# GPS_radiologger_v5_b.net
KiCad netlist of a schematic drawn in EAGLE
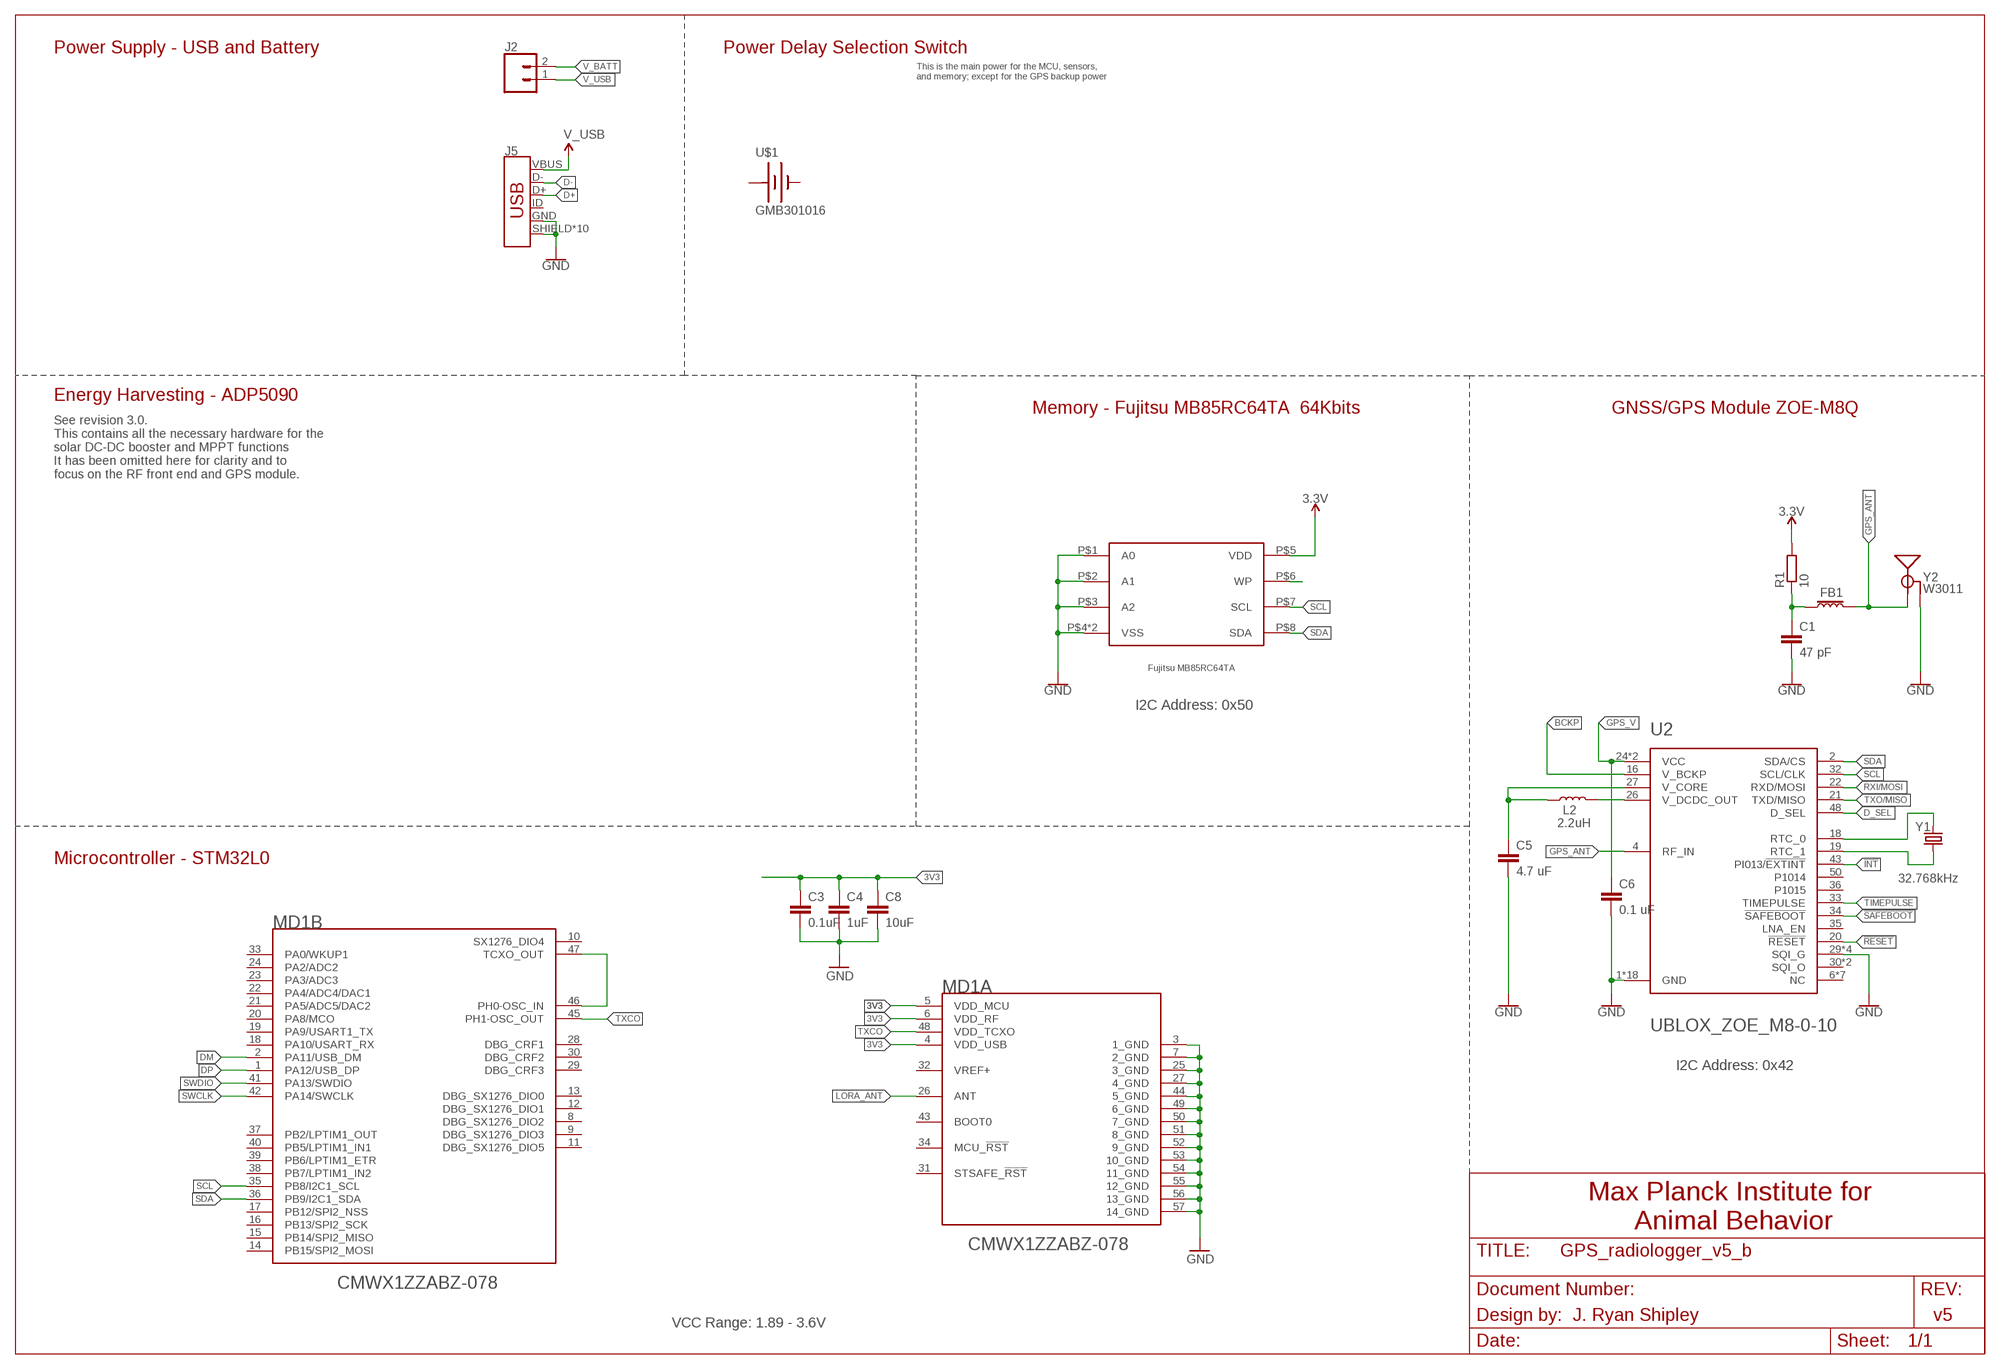
[diagram p0: schematic, sheet 1]

(export (version "E")
  (design (tool "Eeschema 10.0.6"))
  (components
    (comp (ref "C1")
      (value "47 pF")
      (footprint "eagle-import:C0201")
      (libsource (lib "eagle-import") (part "C-EUC0201"))
    )
    (comp (ref "C3")
      (value "0.1uF")
      (footprint "eagle-import:C0201")
      (libsource (lib "eagle-import") (part "C-EUC0201"))
    )
    (comp (ref "C4")
      (value "1uF")
      (footprint "eagle-import:C0201")
      (libsource (lib "eagle-import") (part "C-EUC0201"))
    )
    (comp (ref "C5")
      (value "4.7 uF")
      (footprint "eagle-import:C0201")
      (libsource (lib "eagle-import") (part "C-EUC0201"))
    )
    (comp (ref "C6")
      (value "0.1 uF")
      (footprint "eagle-import:C0201")
      (libsource (lib "eagle-import") (part "C-EUC0201"))
    )
    (comp (ref "C8")
      (value "10uF")
      (footprint "eagle-import:C0201")
      (libsource (lib "eagle-import") (part "C-EUC0201"))
    )
    (comp (ref "FB1")
      (value "FERRITE_BEAD-120_OHM-0402")
      (footprint "eagle-import:0402")
      (fields (field (name "MFG_PART") "BLM15HB121SN1D"))
      (libsource (lib "eagle-import") (part "FERRITE_BEAD-120_OHM-0402"))
    )
    (comp (ref "J2")
      (value "CONN_02")
      (footprint "eagle-import:1X02")
      (libsource (lib "eagle-import") (part "CONN_02"))
    )
    (comp (ref "J5")
      (value "USB_MICRO-B_HALF_PTH_MILL")
      (footprint "eagle-import:USB-MICROB-PTH-MILL")
      (libsource (lib "eagle-import") (part "USB_MICRO-B_HALF_PTH_MILL"))
    )
    (comp (ref "L2")
      (value "2.2uH")
      (footprint "eagle-import:0806")
      (libsource (lib "eagle-import") (part "2.2μH_SHIELDED_INDUCTOR"))
    )
    (comp (ref "MD1")
      (value "MURATA_CMWX1ZZABZ-078MURATA_CMWX1ZZABZ-078_0_0")
      (footprint "eagle-import:MURATA_CMWX1ZZABZ-078_0")
      (fields
        (field (name "DIGIKEY_PART_NUMBER") "490-16143-1-ND")
        (field (name "MF") "Murata")
        (field (name "MOUSER_PART_NUMBER") "81-CMWX1ZZABZ-078")
      )
      (libsource (lib "eagle-import") (part "MURATA_CMWX1ZZABZ-078MURATA_CMWX1ZZABZ-078_0_0"))
    )
    (comp (ref "R1")
      (value "10")
      (footprint "eagle-import:R0201")
      (libsource (lib "eagle-import") (part "R-EU_R0201"))
    )
    (comp (ref "U$1")
      (value "GMB301016")
      (footprint "eagle-import:GMB301016")
      (libsource (lib "eagle-import") (part "GMB301016"))
    )
    (comp (ref "U$2")
      (value "MB85RC64TA")
      (footprint "eagle-import:8-SON_2X3")
      (libsource (lib "eagle-import") (part "MB85RC64TA"))
    )
    (comp (ref "U2")
      (value "UBLOX_ZOE_M8-0-10")
      (footprint "eagle-import:UBLOX_ZOE_M8-0-10")
      (libsource (lib "eagle-import") (part "UBLOX_ZOE_M8-0-10"))
    )
    (comp (ref "Y1")
      (value "32.768kHz")
      (footprint "eagle-import:CRYSTAL-SMD-3.2X1.5MM")
      (libsource (lib "eagle-import") (part "CRYSTAL-32.768KHZSMD-3.2X1.5"))
    )
    (comp (ref "Y2")
      (value "W3011")
      (footprint "eagle-import:W3011")
      (libsource (lib "eagle-import") (part "GPS_CHIP_ANTENNAW3011"))
    )
  )
  (nets
    (net (code "1") (name "/+") (class "Default")
      (node (ref "U$1") (pin "+") (pinfunction "+_+") (pintype "power_in"))
    )
    (net (code "2") (name "/-") (class "Default")
      (node (ref "U$1") (pin "-") (pinfunction "-_-") (pintype "power_in"))
    )
    (net (code "3") (name "/VREF+") (class "Default")
      (node (ref "MD1") (pin "32") (pinfunction "VREF+_32") (pintype "power_in"))
    )
    (net (code "4") (name "/~{INT}") (class "Default")
      (node (ref "U2") (pin "43") (pinfunction "PI013/~{EXTINT}_43") (pintype "bidirectional"))
    )
    (net (code "5") (name "/~{RESET}") (class "Default")
      (node (ref "U2") (pin "20") (pinfunction "~{RESET}_20") (pintype "bidirectional"))
    )
    (net (code "6") (name "/~{SAFEBOOT}") (class "Default")
      (node (ref "U2") (pin "34") (pinfunction "~{SAFEBOOT}_34") (pintype "bidirectional"))
    )
    (net (code "7") (name "3.3V") (class "Default")
      (node (ref "R1") (pin "2") (pinfunction "2_2") (pintype "passive"))
      (node (ref "U$2") (pin "P$5") (pinfunction "VDD_P$5") (pintype "bidirectional"))
    )
    (net (code "8") (name "3V3") (class "Default")
      (node (ref "C3") (pin "1") (pinfunction "1_1") (pintype "passive"))
      (node (ref "C4") (pin "1") (pinfunction "1_1") (pintype "passive"))
      (node (ref "C8") (pin "1") (pinfunction "1_1") (pintype "passive"))
      (node (ref "MD1") (pin "4") (pinfunction "VDD_USB_4") (pintype "power_in"))
      (node (ref "MD1") (pin "5") (pinfunction "VDD_MCU_5") (pintype "power_in"))
      (node (ref "MD1") (pin "6") (pinfunction "VDD_RF_6") (pintype "power_in"))
    )
    (net (code "9") (name "BCKP") (class "Default")
      (node (ref "U2") (pin "16") (pinfunction "V_BCKP_16") (pintype "power_in"))
    )
    (net (code "10") (name "D+") (class "Default")
      (node (ref "J5") (pin "D+") (pinfunction "D+_D+") (pintype "bidirectional"))
    )
    (net (code "11") (name "D-") (class "Default")
      (node (ref "J5") (pin "D-") (pinfunction "D-_D-") (pintype "bidirectional"))
    )
    (net (code "12") (name "DM") (class "Default")
      (node (ref "MD1") (pin "2") (pinfunction "PA11/USB_DM_2") (pintype "bidirectional"))
    )
    (net (code "13") (name "DP") (class "Default")
      (node (ref "MD1") (pin "1") (pinfunction "PA12/USB_DP_1") (pintype "bidirectional"))
    )
    (net (code "14") (name "D_SEL") (class "Default")
      (node (ref "U2") (pin "48") (pinfunction "D_SEL_48") (pintype "bidirectional"))
    )
    (net (code "15") (name "GND") (class "Default")
      (node (ref "C1") (pin "2") (pinfunction "2_2") (pintype "passive"))
      (node (ref "C3") (pin "2") (pinfunction "2_2") (pintype "passive"))
      (node (ref "C4") (pin "2") (pinfunction "2_2") (pintype "passive"))
      (node (ref "C5") (pin "2") (pinfunction "2_2") (pintype "passive"))
      (node (ref "C6") (pin "2") (pinfunction "2_2") (pintype "passive"))
      (node (ref "C8") (pin "2") (pinfunction "2_2") (pintype "passive"))
      (node (ref "J5") (pin "GND") (pinfunction "GND_GND") (pintype "power_in"))
      (node (ref "J5") (pin "SHIELD") (pinfunction "SHIELD_SHIELD") (pintype "bidirectional"))
      (node (ref "J5") (pin "SHIELD10") (pinfunction "SHIELD_SHIELD10") (pintype "bidirectional"))
      (node (ref "J5") (pin "SHIELD2") (pinfunction "SHIELD_SHIELD2") (pintype "bidirectional"))
      (node (ref "J5") (pin "SHIELD3") (pinfunction "SHIELD_SHIELD3") (pintype "bidirectional"))
      (node (ref "J5") (pin "SHIELD4") (pinfunction "SHIELD_SHIELD4") (pintype "bidirectional"))
      (node (ref "J5") (pin "SHIELD5") (pinfunction "SHIELD_SHIELD5") (pintype "bidirectional"))
      (node (ref "J5") (pin "SHIELD6") (pinfunction "SHIELD_SHIELD6") (pintype "bidirectional"))
      (node (ref "J5") (pin "SHIELD7") (pinfunction "SHIELD_SHIELD7") (pintype "bidirectional"))
      (node (ref "J5") (pin "SHIELD8") (pinfunction "SHIELD_SHIELD8") (pintype "bidirectional"))
      (node (ref "J5") (pin "SHIELD9") (pinfunction "SHIELD_SHIELD9") (pintype "bidirectional"))
      (node (ref "MD1") (pin "25") (pinfunction "3_GND_25") (pintype "power_in"))
      (node (ref "MD1") (pin "27") (pinfunction "4_GND_27") (pintype "power_in"))
      (node (ref "MD1") (pin "3") (pinfunction "1_GND_3") (pintype "power_in"))
      (node (ref "MD1") (pin "44") (pinfunction "5_GND_44") (pintype "power_in"))
      (node (ref "MD1") (pin "49") (pinfunction "6_GND_49") (pintype "power_in"))
      (node (ref "MD1") (pin "50") (pinfunction "7_GND_50") (pintype "power_in"))
      (node (ref "MD1") (pin "51") (pinfunction "8_GND_51") (pintype "power_in"))
      (node (ref "MD1") (pin "52") (pinfunction "9_GND_52") (pintype "power_in"))
      (node (ref "MD1") (pin "53") (pinfunction "10_GND_53") (pintype "power_in"))
      (node (ref "MD1") (pin "54") (pinfunction "11_GND_54") (pintype "power_in"))
      (node (ref "MD1") (pin "55") (pinfunction "12_GND_55") (pintype "power_in"))
      (node (ref "MD1") (pin "56") (pinfunction "13_GND_56") (pintype "power_in"))
      (node (ref "MD1") (pin "57") (pinfunction "14_GND_57") (pintype "power_in"))
      (node (ref "MD1") (pin "7") (pinfunction "2_GND_7") (pintype "power_in"))
      (node (ref "U$2") (pin "P$1") (pinfunction "A0_P$1") (pintype "bidirectional"))
      (node (ref "U$2") (pin "P$2") (pinfunction "A1_P$2") (pintype "bidirectional"))
      (node (ref "U$2") (pin "P$3") (pinfunction "A2_P$3") (pintype "bidirectional"))
      (node (ref "U$2") (pin "P$4") (pinfunction "VSS_P$4") (pintype "bidirectional"))
      (node (ref "U$2") (pin "P$9") (pinfunction "VSS_P$9") (pintype "bidirectional"))
      (node (ref "U2") (pin "1") (pinfunction "GND_1") (pintype "power_in"))
      (node (ref "U2") (pin "10") (pinfunction "GND_10") (pintype "power_in"))
      (node (ref "U2") (pin "11") (pinfunction "GND_11") (pintype "power_in"))
      (node (ref "U2") (pin "12") (pinfunction "GND_12") (pintype "power_in"))
      (node (ref "U2") (pin "17") (pinfunction "GND_17") (pintype "power_in"))
      (node (ref "U2") (pin "23") (pinfunction "GND_23") (pintype "power_in"))
      (node (ref "U2") (pin "29") (pinfunction "SQI_G_29") (pintype "bidirectional"))
      (node (ref "U2") (pin "3") (pinfunction "GND_3") (pintype "power_in"))
      (node (ref "U2") (pin "31") (pinfunction "SQI_G_31") (pintype "bidirectional"))
      (node (ref "U2") (pin "37") (pinfunction "GND_37") (pintype "power_in"))
      (node (ref "U2") (pin "38") (pinfunction "GND_38") (pintype "power_in"))
      (node (ref "U2") (pin "39") (pinfunction "GND_39") (pintype "power_in"))
      (node (ref "U2") (pin "40") (pinfunction "GND_40") (pintype "power_in"))
      (node (ref "U2") (pin "41") (pinfunction "GND_41") (pintype "power_in"))
      (node (ref "U2") (pin "44") (pinfunction "GND_44") (pintype "power_in"))
      (node (ref "U2") (pin "46") (pinfunction "SQI_G_46") (pintype "bidirectional"))
      (node (ref "U2") (pin "47") (pinfunction "SQI_G_47") (pintype "bidirectional"))
      (node (ref "U2") (pin "49") (pinfunction "GND_49") (pintype "power_in"))
      (node (ref "U2") (pin "5") (pinfunction "GND_5") (pintype "power_in"))
      (node (ref "U2") (pin "7") (pinfunction "GND_7") (pintype "power_in"))
      (node (ref "U2") (pin "8") (pinfunction "GND_8") (pintype "power_in"))
      (node (ref "U2") (pin "9") (pinfunction "GND_9") (pintype "power_in"))
      (node (ref "Y2") (pin "2") (pinfunction "GND_2") (pintype "bidirectional"))
      (node (ref "Y2") (pin "3") (pinfunction "GND_3") (pintype "bidirectional"))
    )
    (net (code "16") (name "GPS_ANT") (class "Default")
      (node (ref "FB1") (pin "1") (pinfunction "1_1") (pintype "passive"))
      (node (ref "U2") (pin "4") (pinfunction "RF_IN_4") (pintype "bidirectional"))
      (node (ref "Y2") (pin "1") (pinfunction "SIGNAL_1") (pintype "bidirectional"))
    )
    (net (code "17") (name "GPS_V") (class "Default")
      (node (ref "C6") (pin "1") (pinfunction "1_1") (pintype "passive"))
      (node (ref "U2") (pin "24") (pinfunction "VCC_24") (pintype "power_in"))
      (node (ref "U2") (pin "25") (pinfunction "VCC_25") (pintype "power_in"))
    )
    (net (code "18") (name "LORA_ANT") (class "Default")
      (node (ref "MD1") (pin "26") (pinfunction "ANT_26") (pintype "bidirectional"))
    )
    (net (code "19") (name "Net-(C1-Pad1)") (class "Default")
      (node (ref "C1") (pin "1") (pinfunction "1_1") (pintype "passive"))
      (node (ref "FB1") (pin "2") (pinfunction "2_2") (pintype "passive"))
      (node (ref "R1") (pin "1") (pinfunction "1_1") (pintype "passive"))
    )
    (net (code "20") (name "Net-(MD1B-PH0-OSC_IN)") (class "Default")
      (node (ref "MD1") (pin "46") (pinfunction "PH0-OSC_IN_46") (pintype "bidirectional"))
      (node (ref "MD1") (pin "47") (pinfunction "TCXO_OUT_47") (pintype "output"))
    )
    (net (code "21") (name "Net-(U2-RTC_0)") (class "Default")
      (node (ref "U2") (pin "18") (pinfunction "RTC_0_18") (pintype "bidirectional"))
      (node (ref "Y1") (pin "P$2") (pinfunction "2_P$2") (pintype "passive"))
    )
    (net (code "22") (name "Net-(U2-RTC_1)") (class "Default")
      (node (ref "U2") (pin "19") (pinfunction "RTC_1_19") (pintype "bidirectional"))
      (node (ref "Y1") (pin "P$1") (pinfunction "1_P$1") (pintype "passive"))
    )
    (net (code "23") (name "Net-(U2-V_CORE)") (class "Default")
      (node (ref "C5") (pin "1") (pinfunction "1_1") (pintype "passive"))
      (node (ref "L2") (pin "1") (pinfunction "1_1") (pintype "passive"))
      (node (ref "U2") (pin "27") (pinfunction "V_CORE_27") (pintype "power_in"))
    )
    (net (code "24") (name "Net-(U2-V_DCDC_OUT)") (class "Default")
      (node (ref "L2") (pin "2") (pinfunction "2_2") (pintype "passive"))
      (node (ref "U2") (pin "26") (pinfunction "V_DCDC_OUT_26") (pintype "power_in"))
    )
    (net (code "25") (name "RXI{slash}MOSI") (class "Default")
      (node (ref "U2") (pin "22") (pinfunction "RXD/MOSI_22") (pintype "bidirectional"))
    )
    (net (code "26") (name "SCL") (class "Default")
      (node (ref "MD1") (pin "35") (pinfunction "PB8/I2C1_SCL_35") (pintype "bidirectional"))
      (node (ref "U$2") (pin "P$7") (pinfunction "SCL_P$7") (pintype "bidirectional"))
      (node (ref "U2") (pin "32") (pinfunction "SCL/CLK_32") (pintype "bidirectional"))
    )
    (net (code "27") (name "SDA") (class "Default")
      (node (ref "MD1") (pin "36") (pinfunction "PB9/I2C1_SDA_36") (pintype "bidirectional"))
      (node (ref "U$2") (pin "P$8") (pinfunction "SDA_P$8") (pintype "bidirectional"))
      (node (ref "U2") (pin "2") (pinfunction "SDA/CS_2") (pintype "bidirectional"))
    )
    (net (code "28") (name "SWCLK") (class "Default")
      (node (ref "MD1") (pin "42") (pinfunction "PA14/SWCLK_42") (pintype "bidirectional"))
    )
    (net (code "29") (name "SWDIO") (class "Default")
      (node (ref "MD1") (pin "41") (pinfunction "PA13/SWDIO_41") (pintype "bidirectional"))
    )
    (net (code "30") (name "TIMEPULSE") (class "Default")
      (node (ref "U2") (pin "33") (pinfunction "TIMEPULSE_33") (pintype "bidirectional"))
    )
    (net (code "31") (name "TXCO") (class "Default")
      (node (ref "MD1") (pin "45") (pinfunction "PH1-OSC_OUT_45") (pintype "bidirectional"))
      (node (ref "MD1") (pin "48") (pinfunction "VDD_TCXO_48") (pintype "power_in"))
    )
    (net (code "32") (name "TXO{slash}MISO") (class "Default")
      (node (ref "U2") (pin "21") (pinfunction "TXD/MISO_21") (pintype "bidirectional"))
    )
    (net (code "33") (name "V_BATT") (class "Default")
      (node (ref "J2") (pin "2") (pinfunction "2_2") (pintype "passive"))
    )
    (net (code "34") (name "V_USB") (class "Default")
      (node (ref "J2") (pin "1") (pinfunction "1_1") (pintype "passive"))
      (node (ref "J5") (pin "VBUS") (pinfunction "VBUS_VBUS") (pintype "power_in"))
    )
    (net (code "35") (name "unconnected-(J5-PadID)") (class "Default")
      (node (ref "J5") (pin "ID") (pinfunction "ID_ID") (pintype "bidirectional"))
    )
    (net (code "36") (name "unconnected-(MD1A-BOOT0-Pad43)") (class "Default")
      (node (ref "MD1") (pin "43") (pinfunction "BOOT0_43") (pintype "input"))
    )
    (net (code "37") (name "unconnected-(MD1A-MCU_~{RST}-Pad34)") (class "Default")
      (node (ref "MD1") (pin "34") (pinfunction "MCU_~{RST}_34") (pintype "bidirectional"))
    )
    (net (code "38") (name "unconnected-(MD1A-STSAFE_~{RST}-Pad31)") (class "Default")
      (node (ref "MD1") (pin "31") (pinfunction "STSAFE_~{RST}_31") (pintype "bidirectional"))
    )
    (net (code "39") (name "unconnected-(MD1B-DBG_CRF1-Pad28)") (class "Default")
      (node (ref "MD1") (pin "28") (pinfunction "DBG_CRF1_28") (pintype "bidirectional"))
    )
    (net (code "40") (name "unconnected-(MD1B-DBG_CRF2-Pad30)") (class "Default")
      (node (ref "MD1") (pin "30") (pinfunction "DBG_CRF2_30") (pintype "bidirectional"))
    )
    (net (code "41") (name "unconnected-(MD1B-DBG_CRF3-Pad29)") (class "Default")
      (node (ref "MD1") (pin "29") (pinfunction "DBG_CRF3_29") (pintype "bidirectional"))
    )
    (net (code "42") (name "unconnected-(MD1B-DBG_SX1276_DIO0-Pad13)") (class "Default")
      (node (ref "MD1") (pin "13") (pinfunction "DBG_SX1276_DIO0_13") (pintype "bidirectional"))
    )
    (net (code "43") (name "unconnected-(MD1B-DBG_SX1276_DIO1-Pad12)") (class "Default")
      (node (ref "MD1") (pin "12") (pinfunction "DBG_SX1276_DIO1_12") (pintype "bidirectional"))
    )
    (net (code "44") (name "unconnected-(MD1B-DBG_SX1276_DIO2-Pad8)") (class "Default")
      (node (ref "MD1") (pin "8") (pinfunction "DBG_SX1276_DIO2_8") (pintype "bidirectional"))
    )
    (net (code "45") (name "unconnected-(MD1B-DBG_SX1276_DIO3-Pad9)") (class "Default")
      (node (ref "MD1") (pin "9") (pinfunction "DBG_SX1276_DIO3_9") (pintype "bidirectional"))
    )
    (net (code "46") (name "unconnected-(MD1B-DBG_SX1276_DIO5-Pad11)") (class "Default")
      (node (ref "MD1") (pin "11") (pinfunction "DBG_SX1276_DIO5_11") (pintype "bidirectional"))
    )
    (net (code "47") (name "unconnected-(MD1B-PA0{slash}WKUP1-Pad33)") (class "Default")
      (node (ref "MD1") (pin "33") (pinfunction "PA0/WKUP1_33") (pintype "bidirectional"))
    )
    (net (code "48") (name "unconnected-(MD1B-PA2{slash}ADC2-Pad24)") (class "Default")
      (node (ref "MD1") (pin "24") (pinfunction "PA2/ADC2_24") (pintype "bidirectional"))
    )
    (net (code "49") (name "unconnected-(MD1B-PA3{slash}ADC3-Pad23)") (class "Default")
      (node (ref "MD1") (pin "23") (pinfunction "PA3/ADC3_23") (pintype "bidirectional"))
    )
    (net (code "50") (name "unconnected-(MD1B-PA4{slash}ADC4{slash}DAC1-Pad22)") (class "Default")
      (node (ref "MD1") (pin "22") (pinfunction "PA4/ADC4/DAC1_22") (pintype "bidirectional"))
    )
    (net (code "51") (name "unconnected-(MD1B-PA5{slash}ADC5{slash}DAC2-Pad21)") (class "Default")
      (node (ref "MD1") (pin "21") (pinfunction "PA5/ADC5/DAC2_21") (pintype "bidirectional"))
    )
    (net (code "52") (name "unconnected-(MD1B-PA8{slash}MCO-Pad20)") (class "Default")
      (node (ref "MD1") (pin "20") (pinfunction "PA8/MCO_20") (pintype "bidirectional"))
    )
    (net (code "53") (name "unconnected-(MD1B-PA9{slash}USART1_TX-Pad19)") (class "Default")
      (node (ref "MD1") (pin "19") (pinfunction "PA9/USART1_TX_19") (pintype "bidirectional"))
    )
    (net (code "54") (name "unconnected-(MD1B-PA10{slash}USART_RX-Pad18)") (class "Default")
      (node (ref "MD1") (pin "18") (pinfunction "PA10/USART_RX_18") (pintype "bidirectional"))
    )
    (net (code "55") (name "unconnected-(MD1B-PB2{slash}LPTIM1_OUT-Pad37)") (class "Default")
      (node (ref "MD1") (pin "37") (pinfunction "PB2/LPTIM1_OUT_37") (pintype "bidirectional"))
    )
    (net (code "56") (name "unconnected-(MD1B-PB5{slash}LPTIM1_IN1-Pad40)") (class "Default")
      (node (ref "MD1") (pin "40") (pinfunction "PB5/LPTIM1_IN1_40") (pintype "bidirectional"))
    )
    (net (code "57") (name "unconnected-(MD1B-PB6{slash}LPTIM1_ETR-Pad39)") (class "Default")
      (node (ref "MD1") (pin "39") (pinfunction "PB6/LPTIM1_ETR_39") (pintype "bidirectional"))
    )
    (net (code "58") (name "unconnected-(MD1B-PB7{slash}LPTIM1_IN2-Pad38)") (class "Default")
      (node (ref "MD1") (pin "38") (pinfunction "PB7/LPTIM1_IN2_38") (pintype "bidirectional"))
    )
    (net (code "59") (name "unconnected-(MD1B-PB12{slash}SPI2_NSS-Pad17)") (class "Default")
      (node (ref "MD1") (pin "17") (pinfunction "PB12/SPI2_NSS_17") (pintype "bidirectional"))
    )
    (net (code "60") (name "unconnected-(MD1B-PB13{slash}SPI2_SCK-Pad16)") (class "Default")
      (node (ref "MD1") (pin "16") (pinfunction "PB13/SPI2_SCK_16") (pintype "bidirectional"))
    )
    (net (code "61") (name "unconnected-(MD1B-PB14{slash}SPI2_MISO-Pad15)") (class "Default")
      (node (ref "MD1") (pin "15") (pinfunction "PB14/SPI2_MISO_15") (pintype "bidirectional"))
    )
    (net (code "62") (name "unconnected-(MD1B-PB15{slash}SPI2_MOSI-Pad14)") (class "Default")
      (node (ref "MD1") (pin "14") (pinfunction "PB15/SPI2_MOSI_14") (pintype "bidirectional"))
    )
    (net (code "63") (name "unconnected-(MD1B-SX1276_DIO4-Pad10)") (class "Default")
      (node (ref "MD1") (pin "10") (pinfunction "SX1276_DIO4_10") (pintype "bidirectional"))
    )
    (net (code "64") (name "unconnected-(U$2-WP-PadP$6)") (class "Default")
      (node (ref "U$2") (pin "P$6") (pinfunction "WP_P$6") (pintype "bidirectional"))
    )
    (net (code "65") (name "unconnected-(U2-LNA_EN-Pad35)") (class "Default")
      (node (ref "U2") (pin "35") (pinfunction "LNA_EN_35") (pintype "bidirectional"))
    )
    (net (code "66") (name "unconnected-(U2-NC-Pad6)") (class "Default")
      (node (ref "U2") (pin "6") (pinfunction "NC_6") (pintype "no_connect"))
    )
    (net (code "67") (name "unconnected-(U2-NC-Pad13)") (class "Default")
      (node (ref "U2") (pin "13") (pinfunction "NC_13") (pintype "no_connect"))
    )
    (net (code "68") (name "unconnected-(U2-NC-Pad14)") (class "Default")
      (node (ref "U2") (pin "14") (pinfunction "NC_14") (pintype "no_connect"))
    )
    (net (code "69") (name "unconnected-(U2-NC-Pad15)") (class "Default")
      (node (ref "U2") (pin "15") (pinfunction "NC_15") (pintype "no_connect"))
    )
    (net (code "70") (name "unconnected-(U2-NC-Pad28)") (class "Default")
      (node (ref "U2") (pin "28") (pinfunction "NC_28") (pintype "no_connect"))
    )
    (net (code "71") (name "unconnected-(U2-NC-Pad42)") (class "Default")
      (node (ref "U2") (pin "42") (pinfunction "NC_42") (pintype "no_connect"))
    )
    (net (code "72") (name "unconnected-(U2-NC-Pad51)") (class "Default")
      (node (ref "U2") (pin "51") (pinfunction "NC_51") (pintype "no_connect"))
    )
    (net (code "73") (name "unconnected-(U2-P1014-Pad50)") (class "Default")
      (node (ref "U2") (pin "50") (pinfunction "P1014_50") (pintype "bidirectional"))
    )
    (net (code "74") (name "unconnected-(U2-P1015-Pad36)") (class "Default")
      (node (ref "U2") (pin "36") (pinfunction "P1015_36") (pintype "bidirectional"))
    )
    (net (code "75") (name "unconnected-(U2-SQI_O-Pad30)") (class "Default")
      (node (ref "U2") (pin "30") (pinfunction "SQI_O_30") (pintype "no_connect"))
    )
    (net (code "76") (name "unconnected-(U2-SQI_O-Pad45)") (class "Default")
      (node (ref "U2") (pin "45") (pinfunction "SQI_O_45") (pintype "no_connect"))
    )
  )
)
